# Regulators.net
KiCad netlist of a schematic drawn in Altium Designer
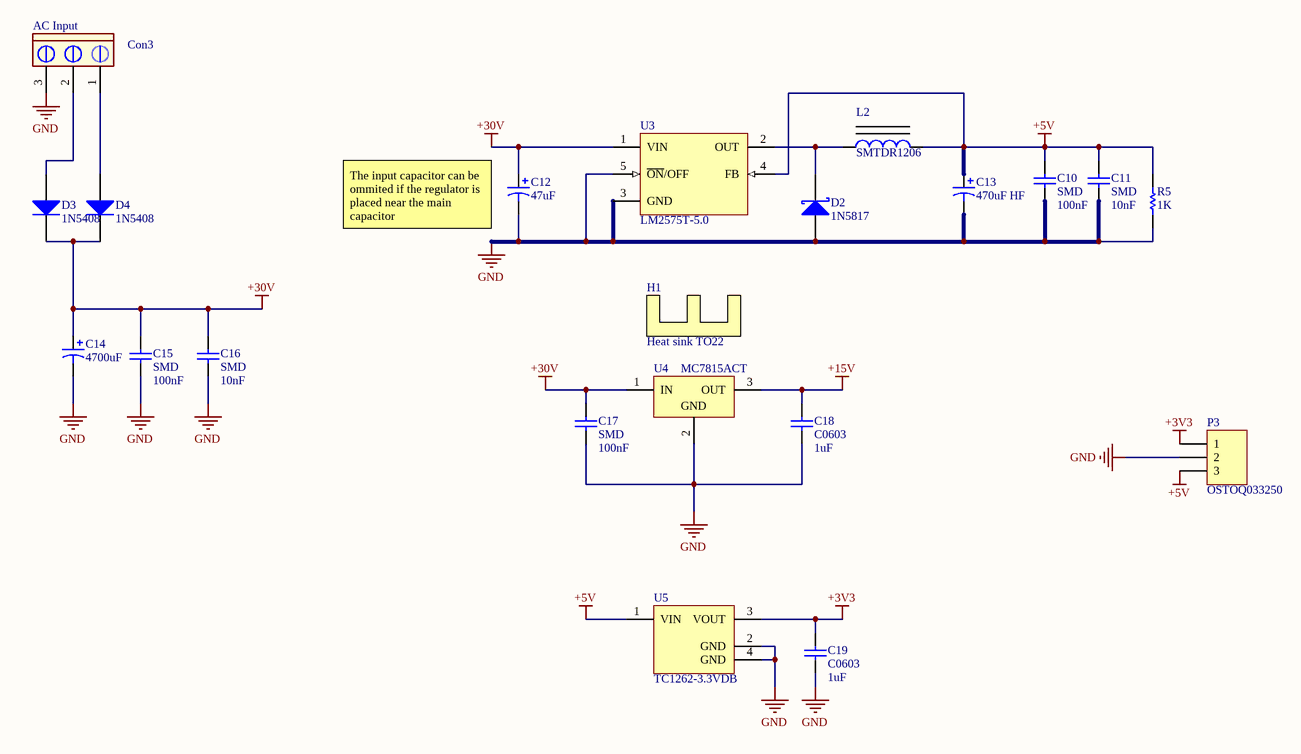
[diagram p0: Regulators.SchDoc]

(export (version "E")
  (design (tool "Eeschema 10.0.6"))
  (components
    (comp (ref "C10")
      (value "SMD")
      (footprint "1206")
      (description "Ceramic Chip Capacitor - Standard")
      (fields (field (name "ALTIUM_VALUE") "100nF") (field (name "PUBLISHER") "Altium Limited"))
      (libsource (lib "KEMET Chip Capacitor") (part "C1206"))
    )
    (comp (ref "C11")
      (value "SMD")
      (footprint "1206")
      (description "Ceramic Chip Capacitor - Standard")
      (fields (field (name "ALTIUM_VALUE") "10nF") (field (name "PUBLISHER") "Altium Limited"))
      (libsource (lib "KEMET Chip Capacitor") (part "C1206"))
    )
    (comp (ref "C12")
      (value "47uF")
      (footprint "CAPPR2.5-6.3X11")
      (description "Aluminum Electrolytic Capacitor, Radial Style with Long Leads: 47uF, 50V")
      (fields (field (name "PUBLISHER") "Altium Limited"))
      (libsource (lib "Vishay Roederstein Electrolytic Radial-Lead Capacitor") (part "EKE00BA247H00"))
    )
    (comp (ref "C13")
      (value "470uF HF")
      (footprint "CAPPR5-10X20")
      (description "Aluminum Electrolytic Capacitor, Radial Style with Long Leads: 470uF, 25V")
      (fields (field (name "PUBLISHER") "Altium Limited"))
      (libsource (lib "Vishay Roederstein Electrolytic Radial-Lead Capacitor") (part "EKC00DE347E00"))
    )
    (comp (ref "C14")
      (value "4700uF")
      (footprint "Capacitor 23x48 (DxH)")
      (description "Generic Electrolytic Capacitor")
      (libsource (lib "NXT - Capacitor") (part "Generic Electrolytic Capacitor"))
    )
    (comp (ref "C15")
      (value "SMD")
      (footprint "1206")
      (description "Ceramic Chip Capacitor - Standard")
      (fields (field (name "ALTIUM_VALUE") "100nF") (field (name "PUBLISHER") "Altium Limited"))
      (libsource (lib "KEMET Chip Capacitor") (part "C1206"))
    )
    (comp (ref "C16")
      (value "SMD")
      (footprint "1206")
      (description "Ceramic Chip Capacitor - Standard")
      (fields (field (name "ALTIUM_VALUE") "10nF") (field (name "PUBLISHER") "Altium Limited"))
      (libsource (lib "KEMET Chip Capacitor") (part "C1206"))
    )
    (comp (ref "C17")
      (value "SMD")
      (footprint "1206")
      (description "Ceramic Chip Capacitor - Standard")
      (fields (field (name "ALTIUM_VALUE") "100nF") (field (name "PUBLISHER") "Altium Limited"))
      (libsource (lib "KEMET Chip Capacitor") (part "C1206"))
    )
    (comp (ref "C18")
      (value "C0603")
      (footprint "0603")
      (description "C1608X7R1C105K X7R")
      (fields (field (name "ALTIUM_VALUE") "1uF") (field (name "PUBLISHER") "Altium Limited"))
      (libsource (lib "KEMET Chip Capacitor") (part "C0603"))
    )
    (comp (ref "C19")
      (value "C0603")
      (footprint "0603")
      (description "C1608X7R1C105K X7R")
      (fields (field (name "ALTIUM_VALUE") "1uF") (field (name "PUBLISHER") "Altium Limited"))
      (libsource (lib "KEMET Chip Capacitor") (part "C0603"))
    )
    (comp (ref "Con3")
      (value "AC Input")
      (footprint "My_CN3")
      (description "Connector green screw")
      (libsource (lib "Mylib") (part "CON3 pin Green"))
    )
    (comp (ref "D2")
      (value "1N5817")
      (footprint "DO-41")
      (description "Schottky Rectifier")
      (fields (field (name "PUBLISHER") "Altium Limited"))
      (libsource (lib "IR Rectifier - Schottky") (part "1N6095"))
    )
    (comp (ref "D3")
      (value "1N5408")
      (footprint "Vertical DO-201AD")
      (description "3 Amp Medium Power Silicon Rectifier Diode")
      (fields (field (name "PUBLISHER") "Altium Limited"))
      (libsource (lib "Miscellaneous Devices") (part "Diode 1N5408"))
    )
    (comp (ref "D4")
      (value "1N5408")
      (footprint "Vertical DO-201AD")
      (description "3 Amp Medium Power Silicon Rectifier Diode")
      (fields (field (name "PUBLISHER") "Altium Limited"))
      (libsource (lib "Miscellaneous Devices") (part "Diode 1N5408"))
    )
    (comp (ref "H1")
      (value "Heat sink TO22")
      (footprint "My_Heat_sink_TO22")
      (description "Heat sink for TO22")
      (libsource (lib "Mylib") (part "Heat sink TO22"))
    )
    (comp (ref "L2")
      (value "SMTDR1206")
      (footprint "SMTDR1206 Inductor")
      (description "Ferrite Inductor")
      (libsource (lib "NXT - Inductors") (part "Ferrite Inductor"))
    )
    (comp (ref "P3")
      (value "XY2500R-F 3P")
      (footprint "OSTOQ033250")
      (description "HEADER 3P P/CI 90gra VERDE P=3.81MM XY2500R-F")
      (fields
        (field (name "MANUFACTURER") "On Shore Technology Inc.")
        (field (name "MANUFACTURER PART NUMBER") "OSTOQ033250")
      )
      (libsource (lib "NXT - Connectors") (part "XY2500R-F 3P"))
    )
    (comp (ref "R5")
      (value "1K")
      (footprint "ERA-0603")
      (fields (field (name "PUBLISHER") "Altium Limited"))
      (libsource (lib "Panasonic Resistor") (part "ERA3Y"))
    )
    (comp (ref "U3")
      (value "LM2575T-5.0")
      (footprint "T05A")
      (description "SIMPLE SWITCHER® 1A Step-Down Voltage Regulator, 5-pin TO-220")
      (fields (field (name "MANUFACTURER") "National Semiconductor"))
      (libsource (lib "National Semiconductor Switcher") (part "LM2575T-5.0"))
    )
    (comp (ref "U4")
      (value "MC7815ACT")
      (footprint "221A-04")
      (description "3-Terminal Positive Fixed Voltage Regulator")
      (fields (field (name "PUBLISHER") "Altium Limited"))
      (libsource (lib "Motorola Power Mgt Voltage Regulator") (part "MC7815ACT"))
    )
    (comp (ref "U5")
      (value "TC1262-3.3VDB")
      (footprint "SOT-223-DB3_N")
      (description "500mA Fixed Output CMOS LDO, 3-Pin SOT-223, Extended Temperature")
      (fields (field (name "MANUFACTURER") "Microchip"))
      (libsource (lib "Microchip Power Management Line Regulator") (part "TC1262-3.3VDB"))
    )
  )
  (nets
    (net (code "1") (name "+3V3") (class "Default")
      (node (ref "C19") (pin "2") (pinfunction "2_2") (pintype "passive"))
      (node (ref "P3") (pin "1") (pinfunction "1_1") (pintype "passive"))
      (node (ref "U5") (pin "3") (pinfunction "VOUT_3") (pintype "power_in"))
    )
    (net (code "2") (name "+5V") (class "Default")
      (node (ref "C10") (pin "2") (pinfunction "2_2") (pintype "passive"))
      (node (ref "C11") (pin "2") (pinfunction "2_2") (pintype "passive"))
      (node (ref "C13") (pin "1") (pinfunction "1_1") (pintype "passive"))
      (node (ref "L2") (pin "2") (pinfunction "2_2") (pintype "passive"))
      (node (ref "P3") (pin "3") (pinfunction "3_3") (pintype "passive"))
      (node (ref "R5") (pin "2") (pinfunction "2_2") (pintype "passive"))
      (node (ref "U3") (pin "4") (pinfunction "FB_4") (pintype "input"))
      (node (ref "U5") (pin "1") (pinfunction "VIN_1") (pintype "power_in"))
    )
    (net (code "3") (name "+15V") (class "Default")
      (node (ref "C18") (pin "2") (pinfunction "2_2") (pintype "passive"))
      (node (ref "U4") (pin "3") (pinfunction "OUT_3") (pintype "power_in"))
    )
    (net (code "4") (name "+30V") (class "Default")
      (node (ref "C12") (pin "1") (pinfunction "1_1") (pintype "passive"))
      (node (ref "C14") (pin "1") (pinfunction "1_1") (pintype "passive"))
      (node (ref "C15") (pin "2") (pinfunction "2_2") (pintype "passive"))
      (node (ref "C16") (pin "2") (pinfunction "2_2") (pintype "passive"))
      (node (ref "C17") (pin "2") (pinfunction "2_2") (pintype "passive"))
      (node (ref "D3") (pin "2") (pinfunction "K_2") (pintype "passive"))
      (node (ref "D4") (pin "2") (pinfunction "K_2") (pintype "passive"))
      (node (ref "U3") (pin "1") (pinfunction "VIN_1") (pintype "power_in"))
      (node (ref "U4") (pin "1") (pinfunction "IN_1") (pintype "power_in"))
    )
    (net (code "5") (name "GND") (class "Default")
      (node (ref "C10") (pin "1") (pinfunction "1_1") (pintype "passive"))
      (node (ref "C11") (pin "1") (pinfunction "1_1") (pintype "passive"))
      (node (ref "C12") (pin "2") (pinfunction "2_2") (pintype "passive"))
      (node (ref "C13") (pin "2") (pinfunction "2_2") (pintype "passive"))
      (node (ref "C14") (pin "2") (pinfunction "2_2") (pintype "passive"))
      (node (ref "C15") (pin "1") (pinfunction "1_1") (pintype "passive"))
      (node (ref "C16") (pin "1") (pinfunction "1_1") (pintype "passive"))
      (node (ref "C17") (pin "1") (pinfunction "1_1") (pintype "passive"))
      (node (ref "C18") (pin "1") (pinfunction "1_1") (pintype "passive"))
      (node (ref "C19") (pin "1") (pinfunction "1_1") (pintype "passive"))
      (node (ref "Con3") (pin "3") (pinfunction "3_3") (pintype "passive"))
      (node (ref "D2") (pin "1") (pinfunction "A_1") (pintype "passive"))
      (node (ref "P3") (pin "2") (pinfunction "2_2") (pintype "passive"))
      (node (ref "R5") (pin "1") (pinfunction "1_1") (pintype "passive"))
      (node (ref "U3") (pin "3") (pinfunction "GND_3") (pintype "power_in"))
      (node (ref "U3") (pin "5") (pinfunction "~{ON}/OFF_5") (pintype "input"))
      (node (ref "U4") (pin "2") (pinfunction "GND_2") (pintype "power_in"))
      (node (ref "U5") (pin "2") (pinfunction "GND_2") (pintype "power_in"))
      (node (ref "U5") (pin "4") (pinfunction "GND_4") (pintype "power_in"))
    )
    (net (code "6") (name "Net-(D2-K)") (class "Default")
      (node (ref "D2") (pin "2") (pinfunction "K_2") (pintype "passive"))
      (node (ref "L2") (pin "1") (pinfunction "1_1") (pintype "passive"))
      (node (ref "U3") (pin "2") (pinfunction "OUT_2") (pintype "power_in"))
    )
    (net (code "7") (name "Net-(D3-A)") (class "Default")
      (node (ref "Con3") (pin "2") (pinfunction "2_2") (pintype "passive"))
      (node (ref "D3") (pin "1") (pinfunction "A_1") (pintype "passive"))
    )
    (net (code "8") (name "Net-(D4-A)") (class "Default")
      (node (ref "Con3") (pin "1") (pinfunction "1_1") (pintype "passive"))
      (node (ref "D4") (pin "1") (pinfunction "A_1") (pintype "passive"))
    )
  )
)
